# logic.net
KiCad netlist of a schematic drawn in EAGLE
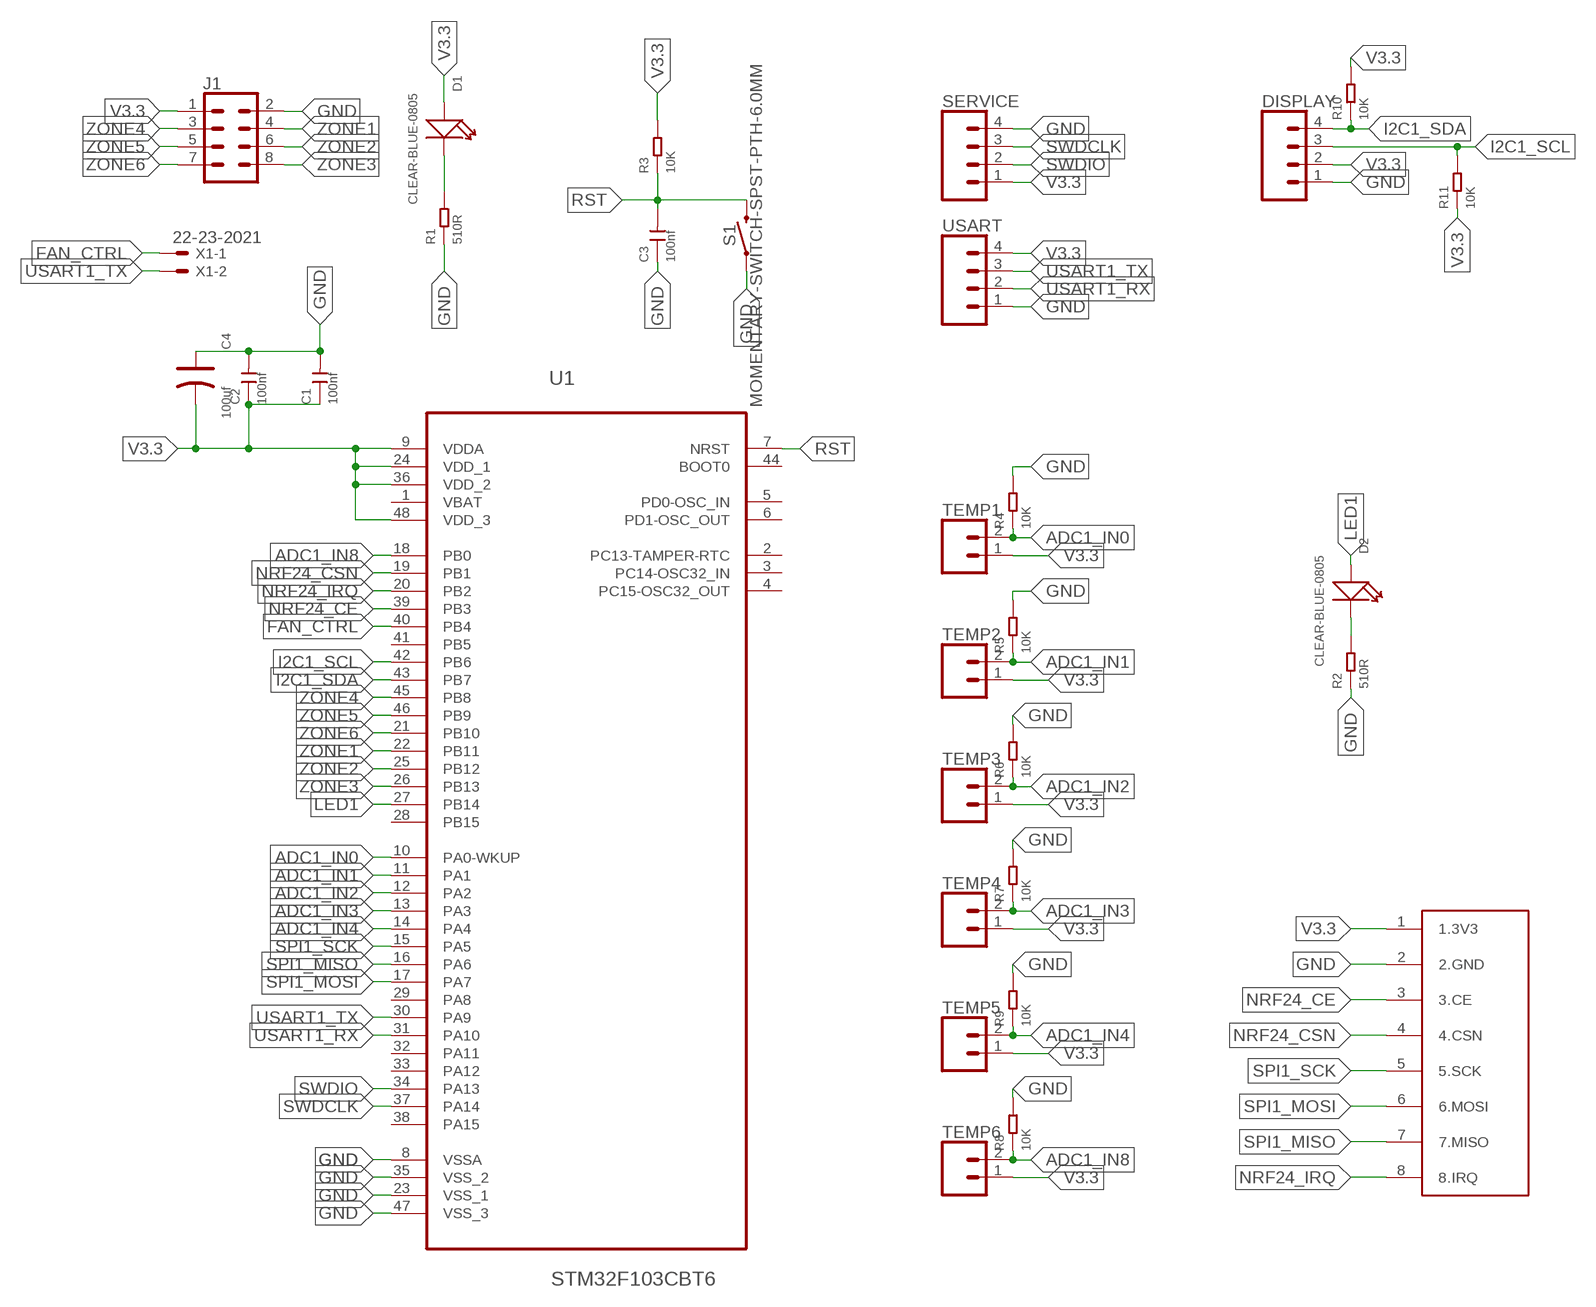
[diagram p0: schematic, sheet 1]

(export (version "E")
  (design (tool "Eeschema 10.0.6"))
  (components
    (comp (ref "C1")
      (value "100nf")
      (footprint "eagle-import:C0805")
      (fields (field (name "MPN") "CC0805KRX7R9BB104"))
      (libsource (lib "eagle-import") (part "CERAMIC-100NF-50V-10%-X7R(0805)"))
    )
    (comp (ref "C2")
      (value "100nf")
      (footprint "eagle-import:C0805")
      (fields (field (name "MPN") "CC0805KRX7R9BB104"))
      (libsource (lib "eagle-import") (part "CERAMIC-100NF-50V-10%-X7R(0805)"))
    )
    (comp (ref "C3")
      (value "100nf")
      (footprint "eagle-import:C0805")
      (fields (field (name "MPN") "CC0805KRX7R9BB104"))
      (libsource (lib "eagle-import") (part "CERAMIC-100NF-50V-10%-X7R(0805)"))
    )
    (comp (ref "C4")
      (value "100uf")
      (footprint "eagle-import:AVX-B")
      (fields (field (name "MPN") "TAJB107M010#NJ"))
      (libsource (lib "eagle-import") (part "TANTALUM-SMD-100UF-10V(AVX-B)"))
    )
    (comp (ref "D1")
      (value "CLEAR-BLUE-0805")
      (footprint "eagle-import:LED-0805")
      (fields (field (name "MPN") "EL-17-215/BHC-AN1P2/3T"))
      (libsource (lib "eagle-import") (part "SMD-LED-CLEAR-BLUE(0805)"))
    )
    (comp (ref "D2")
      (value "CLEAR-BLUE-0805")
      (footprint "eagle-import:LED-0805")
      (fields (field (name "MPN") "EL-17-215/BHC-AN1P2/3T"))
      (libsource (lib "eagle-import") (part "SMD-LED-CLEAR-BLUE(0805)"))
    )
    (comp (ref "DISPLAY")
      (value "CONN_04")
      (footprint "eagle-import:1X04")
      (libsource (lib "eagle-import") (part "CONN_04"))
    )
    (comp (ref "J1")
      (value "CONN_04X2")
      (footprint "eagle-import:2X4")
      (libsource (lib "eagle-import") (part "CONN_04X2"))
    )
    (comp (ref "R1")
      (value "510R")
      (footprint "eagle-import:R0603")
      (fields (field (name "MPN") "RC0603JR-07510RL"))
      (libsource (lib "eagle-import") (part "SMD-RES-510R-5%-1/10W(0603)"))
    )
    (comp (ref "R2")
      (value "510R")
      (footprint "eagle-import:R0603")
      (fields (field (name "MPN") "RC0603JR-07510RL"))
      (libsource (lib "eagle-import") (part "SMD-RES-510R-5%-1/10W(0603)"))
    )
    (comp (ref "R3")
      (value "10K")
      (footprint "eagle-import:R0805")
      (fields (field (name "MPN") "RC0805FR-0710KL"))
      (libsource (lib "eagle-import") (part "SMD-RES-10K-1%-1/8W(0805)"))
    )
    (comp (ref "R4")
      (value "10K")
      (footprint "eagle-import:R0805")
      (fields (field (name "MPN") "RC0805FR-0710KL"))
      (libsource (lib "eagle-import") (part "SMD-RES-10K-1%-1/8W(0805)"))
    )
    (comp (ref "R5")
      (value "10K")
      (footprint "eagle-import:R0805")
      (fields (field (name "MPN") "RC0805FR-0710KL"))
      (libsource (lib "eagle-import") (part "SMD-RES-10K-1%-1/8W(0805)"))
    )
    (comp (ref "R6")
      (value "10K")
      (footprint "eagle-import:R0805")
      (fields (field (name "MPN") "RC0805FR-0710KL"))
      (libsource (lib "eagle-import") (part "SMD-RES-10K-1%-1/8W(0805)"))
    )
    (comp (ref "R7")
      (value "10K")
      (footprint "eagle-import:R0805")
      (fields (field (name "MPN") "RC0805FR-0710KL"))
      (libsource (lib "eagle-import") (part "SMD-RES-10K-1%-1/8W(0805)"))
    )
    (comp (ref "R8")
      (value "10K")
      (footprint "eagle-import:R0805")
      (fields (field (name "MPN") "RC0805FR-0710KL"))
      (libsource (lib "eagle-import") (part "SMD-RES-10K-1%-1/8W(0805)"))
    )
    (comp (ref "R9")
      (value "10K")
      (footprint "eagle-import:R0805")
      (fields (field (name "MPN") "RC0805FR-0710KL"))
      (libsource (lib "eagle-import") (part "SMD-RES-10K-1%-1/8W(0805)"))
    )
    (comp (ref "R10")
      (value "10K")
      (footprint "eagle-import:R0805")
      (fields (field (name "MPN") "RC0805FR-0710KL"))
      (libsource (lib "eagle-import") (part "SMD-RES-10K-1%-1/8W(0805)"))
    )
    (comp (ref "R11")
      (value "10K")
      (footprint "eagle-import:R0805")
      (fields (field (name "MPN") "RC0805FR-0710KL"))
      (libsource (lib "eagle-import") (part "SMD-RES-10K-1%-1/8W(0805)"))
    )
    (comp (ref "S1")
      (value "MOMENTARY-SWITCH-SPST-PTH-6.0MM")
      (footprint "eagle-import:TACTILE_SWITCH_PTH_6.0MM")
      (libsource (lib "eagle-import") (part "MOMENTARY-SWITCH-SPST-PTH-6.0MM"))
    )
    (comp (ref "SERVICE")
      (value "CONN_04")
      (footprint "eagle-import:1X04")
      (libsource (lib "eagle-import") (part "CONN_04"))
    )
    (comp (ref "TEMP1")
      (value "CONN_02")
      (footprint "eagle-import:1X02")
      (libsource (lib "eagle-import") (part "CONN_02"))
    )
    (comp (ref "TEMP2")
      (value "CONN_02")
      (footprint "eagle-import:1X02")
      (libsource (lib "eagle-import") (part "CONN_02"))
    )
    (comp (ref "TEMP3")
      (value "CONN_02")
      (footprint "eagle-import:1X02")
      (libsource (lib "eagle-import") (part "CONN_02"))
    )
    (comp (ref "TEMP4")
      (value "CONN_02")
      (footprint "eagle-import:1X02")
      (libsource (lib "eagle-import") (part "CONN_02"))
    )
    (comp (ref "TEMP5")
      (value "CONN_02")
      (footprint "eagle-import:1X02")
      (libsource (lib "eagle-import") (part "CONN_02"))
    )
    (comp (ref "TEMP6")
      (value "CONN_02")
      (footprint "eagle-import:1X02")
      (libsource (lib "eagle-import") (part "CONN_02"))
    )
    (comp (ref "U$2")
      (value "NRF24L01+")
      (footprint "eagle-import:NRF24L01+")
      (libsource (lib "eagle-import") (part "NRF24L01+"))
    )
    (comp (ref "U1")
      (value "STM32F103CBT6")
      (footprint "eagle-import:QFP50P900X900X160-48N")
      (libsource (lib "eagle-import") (part "STM32F103CBT6"))
    )
    (comp (ref "USART")
      (value "CONN_04")
      (footprint "eagle-import:1X04")
      (libsource (lib "eagle-import") (part "CONN_04"))
    )
    (comp (ref "X1")
      (value "22-23-2021")
      (footprint "eagle-import:22-23-2021")
      (fields (field (name "MF") "MOLEX"))
      (libsource (lib "eagle-import") (part "22-23-2021"))
    )
  )
  (nets
    (net (code "1") (name "/PA11") (class "Default")
      (node (ref "U1") (pin "32") (pinfunction "PA11_32") (pintype "power_in"))
    )
    (net (code "2") (name "ADC1_IN0") (class "Default")
      (node (ref "R4") (pin "1") (pinfunction "1_1") (pintype "passive"))
      (node (ref "TEMP1") (pin "2") (pinfunction "2_2") (pintype "passive"))
      (node (ref "U1") (pin "10") (pinfunction "PA0-WKUP_10") (pintype "bidirectional"))
    )
    (net (code "3") (name "ADC1_IN1") (class "Default")
      (node (ref "R5") (pin "1") (pinfunction "1_1") (pintype "passive"))
      (node (ref "TEMP2") (pin "2") (pinfunction "2_2") (pintype "passive"))
      (node (ref "U1") (pin "11") (pinfunction "PA1_11") (pintype "bidirectional"))
    )
    (net (code "4") (name "ADC1_IN2") (class "Default")
      (node (ref "R6") (pin "1") (pinfunction "1_1") (pintype "passive"))
      (node (ref "TEMP3") (pin "2") (pinfunction "2_2") (pintype "passive"))
      (node (ref "U1") (pin "12") (pinfunction "PA2_12") (pintype "bidirectional"))
    )
    (net (code "5") (name "ADC1_IN3") (class "Default")
      (node (ref "R7") (pin "1") (pinfunction "1_1") (pintype "passive"))
      (node (ref "TEMP4") (pin "2") (pinfunction "2_2") (pintype "passive"))
      (node (ref "U1") (pin "13") (pinfunction "PA3_13") (pintype "bidirectional"))
    )
    (net (code "6") (name "ADC1_IN4") (class "Default")
      (node (ref "R9") (pin "1") (pinfunction "1_1") (pintype "passive"))
      (node (ref "TEMP5") (pin "2") (pinfunction "2_2") (pintype "passive"))
      (node (ref "U1") (pin "14") (pinfunction "PA4_14") (pintype "bidirectional"))
    )
    (net (code "7") (name "ADC1_IN8") (class "Default")
      (node (ref "R8") (pin "1") (pinfunction "1_1") (pintype "passive"))
      (node (ref "TEMP6") (pin "2") (pinfunction "2_2") (pintype "passive"))
      (node (ref "U1") (pin "18") (pinfunction "PB0_18") (pintype "bidirectional"))
    )
    (net (code "8") (name "FAN_CTRL") (class "Default")
      (node (ref "U1") (pin "40") (pinfunction "PB4_40") (pintype "bidirectional"))
      (node (ref "X1") (pin "1") (pinfunction "S_1") (pintype "passive"))
    )
    (net (code "9") (name "GND") (class "Default")
      (node (ref "C1") (pin "2") (pinfunction "2_2") (pintype "passive"))
      (node (ref "C2") (pin "2") (pinfunction "2_2") (pintype "passive"))
      (node (ref "C3") (pin "1") (pinfunction "1_1") (pintype "passive"))
      (node (ref "C4") (pin "+") (pinfunction "+_+") (pintype "passive"))
      (node (ref "DISPLAY") (pin "1") (pinfunction "1_1") (pintype "passive"))
      (node (ref "J1") (pin "2") (pinfunction "2_2") (pintype "passive"))
      (node (ref "R1") (pin "1") (pinfunction "1_1") (pintype "passive"))
      (node (ref "R2") (pin "1") (pinfunction "1_1") (pintype "passive"))
      (node (ref "R4") (pin "2") (pinfunction "2_2") (pintype "passive"))
      (node (ref "R5") (pin "2") (pinfunction "2_2") (pintype "passive"))
      (node (ref "R6") (pin "2") (pinfunction "2_2") (pintype "passive"))
      (node (ref "R7") (pin "2") (pinfunction "2_2") (pintype "passive"))
      (node (ref "R8") (pin "2") (pinfunction "2_2") (pintype "passive"))
      (node (ref "R9") (pin "2") (pinfunction "2_2") (pintype "passive"))
      (node (ref "S1") (pin "1") (pinfunction "1_1") (pintype "passive"))
      (node (ref "SERVICE") (pin "4") (pinfunction "4_4") (pintype "passive"))
      (node (ref "U$2") (pin "2") (pinfunction "2.GND_2") (pintype "bidirectional"))
      (node (ref "U1") (pin "23") (pinfunction "VSS_1_23") (pintype "bidirectional"))
      (node (ref "U1") (pin "35") (pinfunction "VSS_2_35") (pintype "passive"))
      (node (ref "U1") (pin "47") (pinfunction "VSS_3_47") (pintype "passive"))
      (node (ref "U1") (pin "8") (pinfunction "VSSA_8") (pintype "passive"))
      (node (ref "USART") (pin "1") (pinfunction "1_1") (pintype "passive"))
    )
    (net (code "10") (name "I2C1_SCL") (class "Default")
      (node (ref "DISPLAY") (pin "3") (pinfunction "3_3") (pintype "passive"))
      (node (ref "R11") (pin "2") (pinfunction "2_2") (pintype "passive"))
      (node (ref "U1") (pin "42") (pinfunction "PB6_42") (pintype "bidirectional"))
    )
    (net (code "11") (name "I2C1_SDA") (class "Default")
      (node (ref "DISPLAY") (pin "4") (pinfunction "4_4") (pintype "passive"))
      (node (ref "R10") (pin "1") (pinfunction "1_1") (pintype "passive"))
      (node (ref "U1") (pin "43") (pinfunction "PB7_43") (pintype "bidirectional"))
    )
    (net (code "12") (name "LED1") (class "Default")
      (node (ref "D2") (pin "+") (pinfunction "+_+") (pintype "passive"))
      (node (ref "U1") (pin "27") (pinfunction "PB14_27") (pintype "bidirectional"))
    )
    (net (code "13") (name "NRF24_CE") (class "Default")
      (node (ref "U$2") (pin "3") (pinfunction "3.CE_3") (pintype "bidirectional"))
      (node (ref "U1") (pin "39") (pinfunction "PB3_39") (pintype "bidirectional"))
    )
    (net (code "14") (name "NRF24_CSN") (class "Default")
      (node (ref "U$2") (pin "4") (pinfunction "4.CSN_4") (pintype "bidirectional"))
      (node (ref "U1") (pin "19") (pinfunction "PB1_19") (pintype "bidirectional"))
    )
    (net (code "15") (name "NRF24_IRQ") (class "Default")
      (node (ref "U$2") (pin "8") (pinfunction "8.IRQ_8") (pintype "bidirectional"))
      (node (ref "U1") (pin "20") (pinfunction "PB2_20") (pintype "bidirectional"))
    )
    (net (code "16") (name "Net-(D1-Pad-)") (class "Default")
      (node (ref "D1") (pin "-") (pinfunction "-_-") (pintype "passive"))
      (node (ref "R1") (pin "2") (pinfunction "2_2") (pintype "passive"))
    )
    (net (code "17") (name "Net-(D2-Pad-)") (class "Default")
      (node (ref "D2") (pin "-") (pinfunction "-_-") (pintype "passive"))
      (node (ref "R2") (pin "2") (pinfunction "2_2") (pintype "passive"))
    )
    (net (code "18") (name "RST") (class "Default")
      (node (ref "C3") (pin "2") (pinfunction "2_2") (pintype "passive"))
      (node (ref "R3") (pin "1") (pinfunction "1_1") (pintype "passive"))
      (node (ref "S1") (pin "3") (pinfunction "2_3") (pintype "passive"))
      (node (ref "U1") (pin "7") (pinfunction "NRST_7") (pintype "bidirectional"))
    )
    (net (code "19") (name "SPI1_MISO") (class "Default")
      (node (ref "U$2") (pin "7") (pinfunction "7.MISO_7") (pintype "bidirectional"))
      (node (ref "U1") (pin "16") (pinfunction "PA6_16") (pintype "bidirectional"))
    )
    (net (code "20") (name "SPI1_MOSI") (class "Default")
      (node (ref "U$2") (pin "6") (pinfunction "6.MOSI_6") (pintype "bidirectional"))
      (node (ref "U1") (pin "17") (pinfunction "PA7_17") (pintype "bidirectional"))
    )
    (net (code "21") (name "SPI1_SCK") (class "Default")
      (node (ref "U$2") (pin "5") (pinfunction "5.SCK_5") (pintype "bidirectional"))
      (node (ref "U1") (pin "15") (pinfunction "PA5_15") (pintype "bidirectional"))
    )
    (net (code "22") (name "SWDCLK") (class "Default")
      (node (ref "SERVICE") (pin "3") (pinfunction "3_3") (pintype "passive"))
      (node (ref "U1") (pin "37") (pinfunction "PA14_37") (pintype "bidirectional"))
    )
    (net (code "23") (name "SWDIO") (class "Default")
      (node (ref "SERVICE") (pin "2") (pinfunction "2_2") (pintype "passive"))
      (node (ref "U1") (pin "34") (pinfunction "PA13_34") (pintype "bidirectional"))
    )
    (net (code "24") (name "USART1_RX") (class "Default")
      (node (ref "U1") (pin "31") (pinfunction "PA10_31") (pintype "bidirectional"))
      (node (ref "USART") (pin "2") (pinfunction "2_2") (pintype "passive"))
    )
    (net (code "25") (name "USART1_TX") (class "Default")
      (node (ref "U1") (pin "30") (pinfunction "PA9_30") (pintype "bidirectional"))
      (node (ref "USART") (pin "3") (pinfunction "3_3") (pintype "passive"))
      (node (ref "X1") (pin "2") (pinfunction "S_2") (pintype "passive"))
    )
    (net (code "26") (name "V3.3") (class "Default")
      (node (ref "C1") (pin "1") (pinfunction "1_1") (pintype "passive"))
      (node (ref "C2") (pin "1") (pinfunction "1_1") (pintype "passive"))
      (node (ref "C4") (pin "-") (pinfunction "-_-") (pintype "passive"))
      (node (ref "D1") (pin "+") (pinfunction "+_+") (pintype "passive"))
      (node (ref "DISPLAY") (pin "2") (pinfunction "2_2") (pintype "passive"))
      (node (ref "J1") (pin "1") (pinfunction "1_1") (pintype "passive"))
      (node (ref "R10") (pin "2") (pinfunction "2_2") (pintype "passive"))
      (node (ref "R11") (pin "1") (pinfunction "1_1") (pintype "passive"))
      (node (ref "R3") (pin "2") (pinfunction "2_2") (pintype "passive"))
      (node (ref "SERVICE") (pin "1") (pinfunction "1_1") (pintype "passive"))
      (node (ref "TEMP1") (pin "1") (pinfunction "1_1") (pintype "passive"))
      (node (ref "TEMP2") (pin "1") (pinfunction "1_1") (pintype "passive"))
      (node (ref "TEMP3") (pin "1") (pinfunction "1_1") (pintype "passive"))
      (node (ref "TEMP4") (pin "1") (pinfunction "1_1") (pintype "passive"))
      (node (ref "TEMP5") (pin "1") (pinfunction "1_1") (pintype "passive"))
      (node (ref "TEMP6") (pin "1") (pinfunction "1_1") (pintype "passive"))
      (node (ref "U$2") (pin "1") (pinfunction "1.3V3_1") (pintype "bidirectional"))
      (node (ref "U1") (pin "24") (pinfunction "VDD_1_24") (pintype "bidirectional"))
      (node (ref "U1") (pin "36") (pinfunction "VDD_2_36") (pintype "power_in"))
      (node (ref "U1") (pin "48") (pinfunction "VDD_3_48") (pintype "power_in"))
      (node (ref "U1") (pin "9") (pinfunction "VDDA_9") (pintype "power_in"))
      (node (ref "USART") (pin "4") (pinfunction "4_4") (pintype "passive"))
    )
    (net (code "27") (name "ZONE1") (class "Default")
      (node (ref "J1") (pin "4") (pinfunction "4_4") (pintype "passive"))
      (node (ref "U1") (pin "22") (pinfunction "PB11_22") (pintype "bidirectional"))
    )
    (net (code "28") (name "ZONE2") (class "Default")
      (node (ref "J1") (pin "6") (pinfunction "6_6") (pintype "passive"))
      (node (ref "U1") (pin "25") (pinfunction "PB12_25") (pintype "bidirectional"))
    )
    (net (code "29") (name "ZONE3") (class "Default")
      (node (ref "J1") (pin "8") (pinfunction "8_8") (pintype "passive"))
      (node (ref "U1") (pin "26") (pinfunction "PB13_26") (pintype "bidirectional"))
    )
    (net (code "30") (name "ZONE4") (class "Default")
      (node (ref "J1") (pin "3") (pinfunction "3_3") (pintype "passive"))
      (node (ref "U1") (pin "45") (pinfunction "PB8_45") (pintype "bidirectional"))
    )
    (net (code "31") (name "ZONE5") (class "Default")
      (node (ref "J1") (pin "5") (pinfunction "5_5") (pintype "passive"))
      (node (ref "U1") (pin "46") (pinfunction "PB9_46") (pintype "bidirectional"))
    )
    (net (code "32") (name "ZONE6") (class "Default")
      (node (ref "J1") (pin "7") (pinfunction "7_7") (pintype "passive"))
      (node (ref "U1") (pin "21") (pinfunction "PB10_21") (pintype "bidirectional"))
    )
    (net (code "33") (name "unconnected-(U1-BOOT0-Pad44)") (class "Default")
      (node (ref "U1") (pin "44") (pinfunction "BOOT0_44") (pintype "bidirectional"))
    )
    (net (code "34") (name "unconnected-(U1-PA8-Pad29)") (class "Default")
      (node (ref "U1") (pin "29") (pinfunction "PA8_29") (pintype "bidirectional"))
    )
    (net (code "35") (name "unconnected-(U1-PA12-Pad33)") (class "Default")
      (node (ref "U1") (pin "33") (pinfunction "PA12_33") (pintype "bidirectional"))
    )
    (net (code "36") (name "unconnected-(U1-PA15-Pad38)") (class "Default")
      (node (ref "U1") (pin "38") (pinfunction "PA15_38") (pintype "bidirectional"))
    )
    (net (code "37") (name "unconnected-(U1-PB5-Pad41)") (class "Default")
      (node (ref "U1") (pin "41") (pinfunction "PB5_41") (pintype "bidirectional"))
    )
    (net (code "38") (name "unconnected-(U1-PB15-Pad28)") (class "Default")
      (node (ref "U1") (pin "28") (pinfunction "PB15_28") (pintype "bidirectional"))
    )
    (net (code "39") (name "unconnected-(U1-PC13-TAMPER-RTC-Pad2)") (class "Default")
      (node (ref "U1") (pin "2") (pinfunction "PC13-TAMPER-RTC_2") (pintype "bidirectional"))
    )
    (net (code "40") (name "unconnected-(U1-PC14-OSC32_IN-Pad3)") (class "Default")
      (node (ref "U1") (pin "3") (pinfunction "PC14-OSC32_IN_3") (pintype "bidirectional"))
    )
    (net (code "41") (name "unconnected-(U1-PC15-OSC32_OUT-Pad4)") (class "Default")
      (node (ref "U1") (pin "4") (pinfunction "PC15-OSC32_OUT_4") (pintype "bidirectional"))
    )
    (net (code "42") (name "unconnected-(U1-PD0-OSC_IN-Pad5)") (class "Default")
      (node (ref "U1") (pin "5") (pinfunction "PD0-OSC_IN_5") (pintype "bidirectional"))
    )
    (net (code "43") (name "unconnected-(U1-PD1-OSC_OUT-Pad6)") (class "Default")
      (node (ref "U1") (pin "6") (pinfunction "PD1-OSC_OUT_6") (pintype "bidirectional"))
    )
    (net (code "44") (name "unconnected-(U1-VBAT-Pad1)") (class "Default")
      (node (ref "U1") (pin "1") (pinfunction "VBAT_1") (pintype "input"))
    )
  )
)
